# IMU.net
KiCad netlist of a schematic drawn in Altium Designer
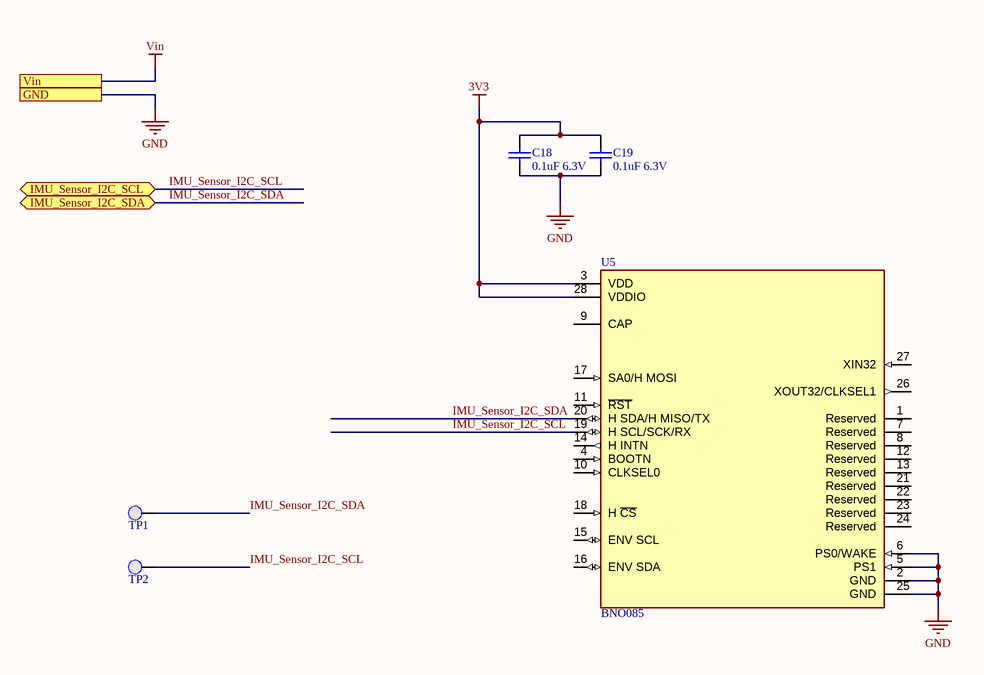
[diagram p0: IMU.SchDoc]

(export (version "E")
  (design (tool "Eeschema 10.0.6"))
  (components
    (comp (ref "C18")
      (value "0.1uF 6.3V")
      (footprint "CAPC0402(1005)60_M")
      (description "CAP 100nF 6.3V ±5% 0402 (1005 Metric) Thickness 0.6mm SMD")
      (fields (field (name "TOLERANCE") "Â±5%"))
      (libsource (lib "Altium Content Vault") (part "CAP"))
    )
    (comp (ref "C19")
      (value "0.1uF 6.3V")
      (footprint "CAPC0402(1005)60_M")
      (description "CAP 100nF 6.3V ±5% 0402 (1005 Metric) Thickness 0.6mm SMD")
      (fields (field (name "TOLERANCE") "Â±5%"))
      (libsource (lib "Altium Content Vault") (part "CAP"))
    )
    (comp (ref "TP1")
      (value "0.1\" Pad")
      (footprint "PCBComponent")
      (libsource (lib "Components - 12.02.20 - 18.05") (part "0.1{dblquote} Pad-A.4"))
    )
    (comp (ref "TP2")
      (value "0.1\" Pad")
      (footprint "PCBComponent")
      (libsource (lib "Components - 12.02.20 - 18.05") (part "0.1{dblquote} Pad-A.4"))
    )
    (comp (ref "U5")
      (value "BNO085")
      (footprint "FP-BNO085-MFG")
      (description "IMU ACCEL/GYRO/MAG I2C 32BIT")
      (fields
        (field (name "OCTOPART") "https://octopart.com/bno085-hillcrest+laboratories-92813482")
        (field (name "MANUFACTURER") "Hillcrest Laboratories, Inc.")
      )
      (libsource (lib "Altium Content Vault") (part "87552c951d161a888c2c69b58ce40bc"))
    )
  )
  (nets
    (net (code "1") (name "/IMU_Sensor_I2C_SCL") (class "Default")
      (node (ref "TP2") (pin "1") (pinfunction "PAD_1") (pintype "passive"))
      (node (ref "U5") (pin "19") (pinfunction "H_SCL/SCK/RX_19") (pintype "bidirectional"))
    )
    (net (code "2") (name "/IMU_Sensor_I2C_SDA") (class "Default")
      (node (ref "TP1") (pin "1") (pinfunction "PAD_1") (pintype "passive"))
      (node (ref "U5") (pin "20") (pinfunction "H_SDA/H_MISO/TX_20") (pintype "bidirectional"))
    )
    (net (code "3") (name "3V3") (class "Default")
      (node (ref "C18") (pin "2") (pinfunction "2_2") (pintype "passive"))
      (node (ref "C19") (pin "2") (pinfunction "2_2") (pintype "passive"))
      (node (ref "U5") (pin "28") (pinfunction "VDDIO_28") (pintype "power_in"))
      (node (ref "U5") (pin "3") (pinfunction "VDD_3") (pintype "power_in"))
    )
    (net (code "4") (name "GND") (class "Default")
      (node (ref "C18") (pin "1") (pinfunction "1_1") (pintype "passive"))
      (node (ref "C19") (pin "1") (pinfunction "1_1") (pintype "passive"))
      (node (ref "U5") (pin "2") (pinfunction "GND_2") (pintype "power_in"))
      (node (ref "U5") (pin "25") (pinfunction "GND_25") (pintype "power_in"))
      (node (ref "U5") (pin "5") (pinfunction "PS1_5") (pintype "input"))
      (node (ref "U5") (pin "6") (pinfunction "PS0/WAKE_6") (pintype "input"))
    )
    (net (code "6") (name "unconnected-(U5-BOOTN-Pad4)") (class "Default")
      (node (ref "U5") (pin "4") (pinfunction "BOOTN_4") (pintype "input"))
    )
    (net (code "7") (name "unconnected-(U5-CAP-Pad9)") (class "Default")
      (node (ref "U5") (pin "9") (pinfunction "CAP_9") (pintype "passive"))
    )
    (net (code "8") (name "unconnected-(U5-CLKSEL0-Pad10)") (class "Default")
      (node (ref "U5") (pin "10") (pinfunction "CLKSEL0_10") (pintype "input"))
    )
    (net (code "9") (name "unconnected-(U5-ENV_SCL-Pad15)") (class "Default")
      (node (ref "U5") (pin "15") (pinfunction "ENV_SCL_15") (pintype "bidirectional"))
    )
    (net (code "10") (name "unconnected-(U5-ENV_SDA-Pad16)") (class "Default")
      (node (ref "U5") (pin "16") (pinfunction "ENV_SDA_16") (pintype "bidirectional"))
    )
    (net (code "11") (name "unconnected-(U5-H_INTN-Pad14)") (class "Default")
      (node (ref "U5") (pin "14") (pinfunction "H_INTN_14") (pintype "output"))
    )
    (net (code "12") (name "unconnected-(U5-H_~{CS}-Pad18)") (class "Default")
      (node (ref "U5") (pin "18") (pinfunction "H_~{CS}_18") (pintype "input"))
    )
    (net (code "13") (name "unconnected-(U5-Reserved-Pad1)") (class "Default")
      (node (ref "U5") (pin "1") (pinfunction "Reserved_1") (pintype "passive"))
    )
    (net (code "14") (name "unconnected-(U5-Reserved-Pad7)") (class "Default")
      (node (ref "U5") (pin "7") (pinfunction "Reserved_7") (pintype "passive"))
    )
    (net (code "15") (name "unconnected-(U5-Reserved-Pad8)") (class "Default")
      (node (ref "U5") (pin "8") (pinfunction "Reserved_8") (pintype "passive"))
    )
    (net (code "16") (name "unconnected-(U5-Reserved-Pad12)") (class "Default")
      (node (ref "U5") (pin "12") (pinfunction "Reserved_12") (pintype "passive"))
    )
    (net (code "17") (name "unconnected-(U5-Reserved-Pad13)") (class "Default")
      (node (ref "U5") (pin "13") (pinfunction "Reserved_13") (pintype "passive"))
    )
    (net (code "18") (name "unconnected-(U5-Reserved-Pad21)") (class "Default")
      (node (ref "U5") (pin "21") (pinfunction "Reserved_21") (pintype "passive"))
    )
    (net (code "19") (name "unconnected-(U5-Reserved-Pad22)") (class "Default")
      (node (ref "U5") (pin "22") (pinfunction "Reserved_22") (pintype "passive"))
    )
    (net (code "20") (name "unconnected-(U5-Reserved-Pad23)") (class "Default")
      (node (ref "U5") (pin "23") (pinfunction "Reserved_23") (pintype "passive"))
    )
    (net (code "21") (name "unconnected-(U5-Reserved-Pad24)") (class "Default")
      (node (ref "U5") (pin "24") (pinfunction "Reserved_24") (pintype "passive"))
    )
    (net (code "22") (name "unconnected-(U5-SA0{slash}H_MOSI-Pad17)") (class "Default")
      (node (ref "U5") (pin "17") (pinfunction "SA0/H_MOSI_17") (pintype "input"))
    )
    (net (code "23") (name "unconnected-(U5-XIN32-Pad27)") (class "Default")
      (node (ref "U5") (pin "27") (pinfunction "XIN32_27") (pintype "input"))
    )
    (net (code "24") (name "unconnected-(U5-XOUT32{slash}CLKSEL1-Pad26)") (class "Default")
      (node (ref "U5") (pin "26") (pinfunction "XOUT32/CLKSEL1_26") (pintype "output"))
    )
    (net (code "25") (name "unconnected-(U5-~{RST}-Pad11)") (class "Default")
      (node (ref "U5") (pin "11") (pinfunction "~{RST}_11") (pintype "input"))
    )
  )
)
